# tiny-usb.net
KiCad netlist of a schematic drawn in EAGLE
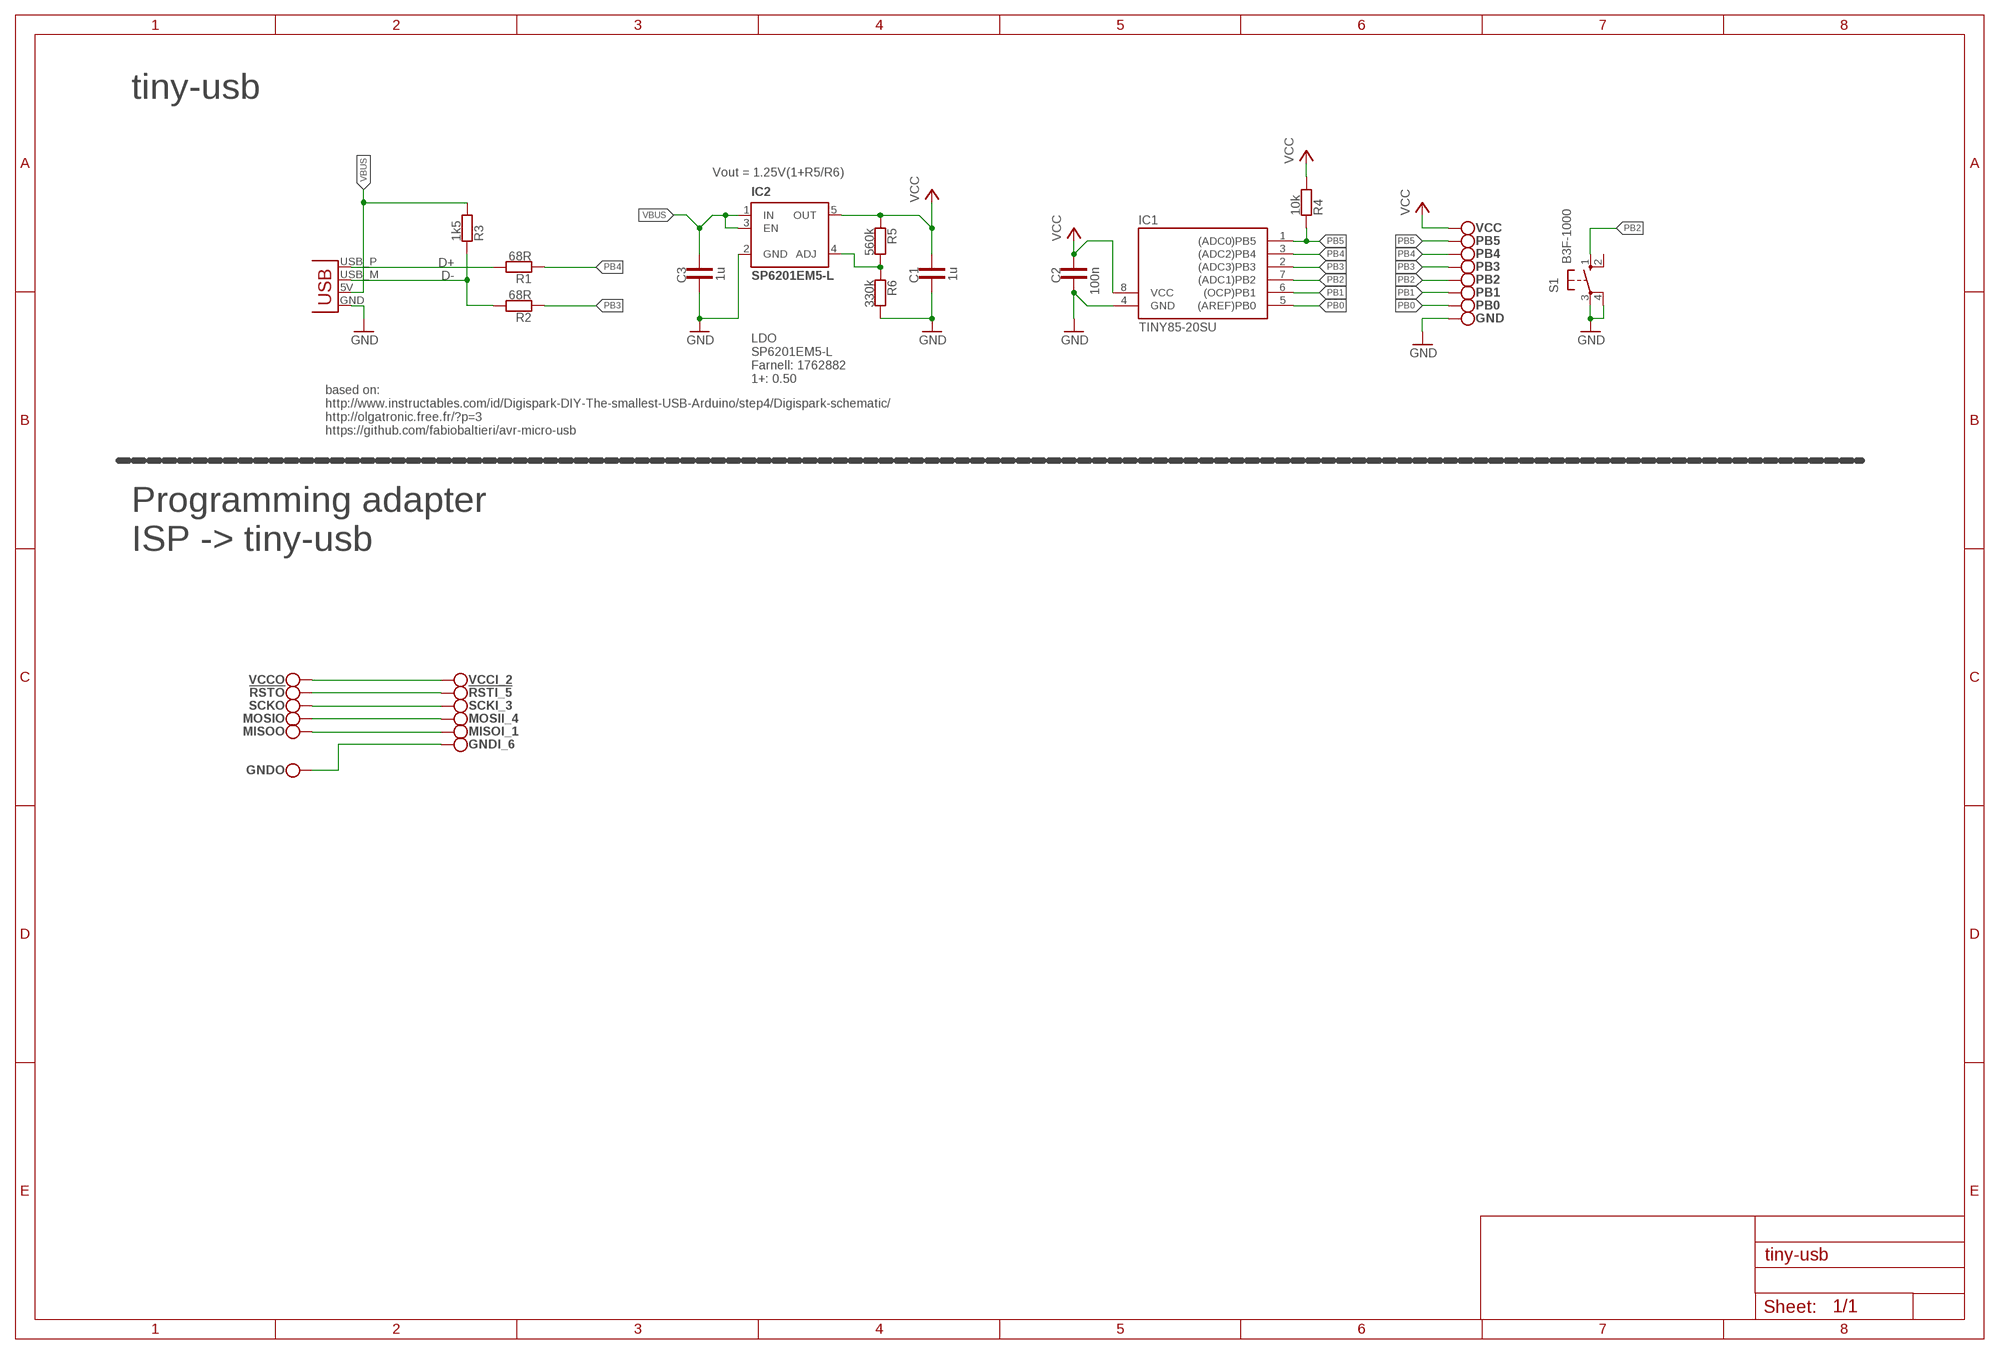
[diagram p0: schematic, sheet 1]

(export (version "E")
  (design (tool "Eeschema 10.0.6"))
  (components
    (comp (ref "!RSTI_5")
      (value "TP_Q3X1.5MM")
      (footprint "eagle-import:PAD_Q1.5X3MM")
      (libsource (lib "eagle-import") (part "TP_Q3X1.5MM"))
    )
    (comp (ref "!RSTO")
      (value "TP_Q3X1.5MM")
      (footprint "eagle-import:PAD_Q1.5X3MM")
      (libsource (lib "eagle-import") (part "TP_Q3X1.5MM"))
    )
    (comp (ref "C1")
      (value "1u")
      (footprint "eagle-import:0603MIL")
      (libsource (lib "eagle-import") (part "C0603"))
    )
    (comp (ref "C2")
      (value "100n")
      (footprint "eagle-import:0603MIL")
      (libsource (lib "eagle-import") (part "C0603"))
    )
    (comp (ref "C3")
      (value "1u")
      (footprint "eagle-import:0603MIL")
      (libsource (lib "eagle-import") (part "C0603"))
    )
    (comp (ref "GND")
      (value "TP_Q3X1.5MM")
      (footprint "eagle-import:PAD_Q1.5X3MM")
      (libsource (lib "eagle-import") (part "TP_Q3X1.5MM"))
    )
    (comp (ref "GNDI_6")
      (value "TP_Q3X1.5MM")
      (footprint "eagle-import:PAD_Q1.5X3MM")
      (libsource (lib "eagle-import") (part "TP_Q3X1.5MM"))
    )
    (comp (ref "GNDO")
      (value "TP_Q3X1.5MM")
      (footprint "eagle-import:PAD_Q1.5X3MM")
      (libsource (lib "eagle-import") (part "TP_Q3X1.5MM"))
    )
    (comp (ref "IC1")
      (value "TINY85-20SU")
      (footprint "eagle-import:SOIC8")
      (libsource (lib "eagle-import") (part "TINY25-20SU"))
    )
    (comp (ref "IC2")
      (value "SP6201EM5-L")
      (footprint "eagle-import:SOT23-5")
      (libsource (lib "eagle-import") (part "SP6201EM5-L"))
    )
    (comp (ref "MISOI_1")
      (value "TP_Q3X1.5MM")
      (footprint "eagle-import:PAD_Q1.5X3MM")
      (libsource (lib "eagle-import") (part "TP_Q3X1.5MM"))
    )
    (comp (ref "MISOO")
      (value "TP_Q3X1.5MM")
      (footprint "eagle-import:PAD_Q1.5X3MM")
      (libsource (lib "eagle-import") (part "TP_Q3X1.5MM"))
    )
    (comp (ref "MOSII_4")
      (value "TP_Q3X1.5MM")
      (footprint "eagle-import:PAD_Q1.5X3MM")
      (libsource (lib "eagle-import") (part "TP_Q3X1.5MM"))
    )
    (comp (ref "MOSIO")
      (value "TP_Q3X1.5MM")
      (footprint "eagle-import:PAD_Q1.5X3MM")
      (libsource (lib "eagle-import") (part "TP_Q3X1.5MM"))
    )
    (comp (ref "PB0")
      (value "TP_Q3X1.5MM")
      (footprint "eagle-import:PAD_Q1.5X3MM")
      (libsource (lib "eagle-import") (part "TP_Q3X1.5MM"))
    )
    (comp (ref "PB1")
      (value "TP_Q3X1.5MM")
      (footprint "eagle-import:PAD_Q1.5X3MM")
      (libsource (lib "eagle-import") (part "TP_Q3X1.5MM"))
    )
    (comp (ref "PB2")
      (value "TP_Q3X1.5MM")
      (footprint "eagle-import:PAD_Q1.5X3MM")
      (libsource (lib "eagle-import") (part "TP_Q3X1.5MM"))
    )
    (comp (ref "PB3")
      (value "TP_Q3X1.5MM")
      (footprint "eagle-import:PAD_Q1.5X3MM")
      (libsource (lib "eagle-import") (part "TP_Q3X1.5MM"))
    )
    (comp (ref "PB4")
      (value "TP_Q3X1.5MM")
      (footprint "eagle-import:PAD_Q1.5X3MM")
      (libsource (lib "eagle-import") (part "TP_Q3X1.5MM"))
    )
    (comp (ref "PB5")
      (value "TP_Q3X1.5MM")
      (footprint "eagle-import:PAD_Q1.5X3MM")
      (libsource (lib "eagle-import") (part "TP_Q3X1.5MM"))
    )
    (comp (ref "R1")
      (value "68R")
      (footprint "eagle-import:0603MIL")
      (libsource (lib "eagle-import") (part "R0603"))
    )
    (comp (ref "R2")
      (value "68R")
      (footprint "eagle-import:0603MIL")
      (libsource (lib "eagle-import") (part "R0603"))
    )
    (comp (ref "R3")
      (value "1k5")
      (footprint "eagle-import:0603MIL")
      (libsource (lib "eagle-import") (part "R0603"))
    )
    (comp (ref "R4")
      (value "10k")
      (footprint "eagle-import:0603MIL")
      (libsource (lib "eagle-import") (part "R0603"))
    )
    (comp (ref "R5")
      (value "560k")
      (footprint "eagle-import:0603MIL")
      (libsource (lib "eagle-import") (part "R0603"))
    )
    (comp (ref "R6")
      (value "330k")
      (footprint "eagle-import:0603MIL")
      (libsource (lib "eagle-import") (part "R0603"))
    )
    (comp (ref "S1")
      (value "B3F-1000")
      (footprint "eagle-import:B3F-10SMD")
      (libsource (lib "eagle-import") (part "10-XXSMD"))
    )
    (comp (ref "SCKI_3")
      (value "TP_Q3X1.5MM")
      (footprint "eagle-import:PAD_Q1.5X3MM")
      (libsource (lib "eagle-import") (part "TP_Q3X1.5MM"))
    )
    (comp (ref "SCKO")
      (value "TP_Q3X1.5MM")
      (footprint "eagle-import:PAD_Q1.5X3MM")
      (libsource (lib "eagle-import") (part "TP_Q3X1.5MM"))
    )
    (comp (ref "VCC")
      (value "TP_Q3X1.5MM")
      (footprint "eagle-import:PAD_Q1.5X3MM")
      (libsource (lib "eagle-import") (part "TP_Q3X1.5MM"))
    )
    (comp (ref "VCCI_2")
      (value "TP_Q3X1.5MM")
      (footprint "eagle-import:PAD_Q1.5X3MM")
      (libsource (lib "eagle-import") (part "TP_Q3X1.5MM"))
    )
    (comp (ref "VCCO")
      (value "TP_Q3X1.5MM")
      (footprint "eagle-import:PAD_Q1.5X3MM")
      (libsource (lib "eagle-import") (part "TP_Q3X1.5MM"))
    )
    (comp (ref "X1")
      (value "USBPCB")
      (footprint "eagle-import:USB-A-PCB")
      (libsource (lib "eagle-import") (part "USBPCB"))
    )
  )
  (nets
    (net (code "1") (name "/D+") (class "Default")
      (node (ref "R1") (pin "2") (pinfunction "2_2") (pintype "passive"))
      (node (ref "X1") (pin "USB_P") (pinfunction "D+_USB_P") (pintype "bidirectional"))
    )
    (net (code "2") (name "/D-") (class "Default")
      (node (ref "R2") (pin "2") (pinfunction "2_2") (pintype "passive"))
      (node (ref "R3") (pin "1") (pinfunction "1_1") (pintype "passive"))
      (node (ref "X1") (pin "USB_M") (pinfunction "D-_USB_M") (pintype "bidirectional"))
    )
    (net (code "3") (name "GND") (class "Default")
      (node (ref "C1") (pin "2") (pinfunction "2_2") (pintype "passive"))
      (node (ref "C2") (pin "2") (pinfunction "2_2") (pintype "passive"))
      (node (ref "C3") (pin "2") (pinfunction "2_2") (pintype "passive"))
      (node (ref "GND") (pin "1") (pinfunction "P$1_1") (pintype "bidirectional"))
      (node (ref "IC1") (pin "4") (pinfunction "GND_4") (pintype "power_in"))
      (node (ref "IC2") (pin "2") (pinfunction "GND_2") (pintype "bidirectional"))
      (node (ref "R6") (pin "2") (pinfunction "2_2") (pintype "passive"))
      (node (ref "S1") (pin "3") (pinfunction "P_3") (pintype "passive"))
      (node (ref "S1") (pin "4") (pinfunction "P1_4") (pintype "passive"))
      (node (ref "X1") (pin "GND") (pinfunction "GND_GND") (pintype "bidirectional"))
    )
    (net (code "4") (name "Net-(!RSTI_5-P$1)") (class "Default")
      (node (ref "!RSTI_5") (pin "1") (pinfunction "P$1_1") (pintype "bidirectional"))
      (node (ref "!RSTO") (pin "1") (pinfunction "P$1_1") (pintype "bidirectional"))
    )
    (net (code "5") (name "Net-(GNDI_6-P$1)") (class "Default")
      (node (ref "GNDI_6") (pin "1") (pinfunction "P$1_1") (pintype "bidirectional"))
      (node (ref "GNDO") (pin "1") (pinfunction "P$1_1") (pintype "bidirectional"))
    )
    (net (code "6") (name "Net-(IC2-ADJ)") (class "Default")
      (node (ref "IC2") (pin "4") (pinfunction "ADJ_4") (pintype "bidirectional"))
      (node (ref "R5") (pin "2") (pinfunction "2_2") (pintype "passive"))
      (node (ref "R6") (pin "1") (pinfunction "1_1") (pintype "passive"))
    )
    (net (code "7") (name "Net-(MISOI_1-P$1)") (class "Default")
      (node (ref "MISOI_1") (pin "1") (pinfunction "P$1_1") (pintype "bidirectional"))
      (node (ref "MISOO") (pin "1") (pinfunction "P$1_1") (pintype "bidirectional"))
    )
    (net (code "8") (name "Net-(MOSII_4-P$1)") (class "Default")
      (node (ref "MOSII_4") (pin "1") (pinfunction "P$1_1") (pintype "bidirectional"))
      (node (ref "MOSIO") (pin "1") (pinfunction "P$1_1") (pintype "bidirectional"))
    )
    (net (code "9") (name "Net-(SCKI_3-P$1)") (class "Default")
      (node (ref "SCKI_3") (pin "1") (pinfunction "P$1_1") (pintype "bidirectional"))
      (node (ref "SCKO") (pin "1") (pinfunction "P$1_1") (pintype "bidirectional"))
    )
    (net (code "10") (name "Net-(VCCI_2-P$1)") (class "Default")
      (node (ref "VCCI_2") (pin "1") (pinfunction "P$1_1") (pintype "bidirectional"))
      (node (ref "VCCO") (pin "1") (pinfunction "P$1_1") (pintype "bidirectional"))
    )
    (net (code "11") (name "PB0") (class "Default")
      (node (ref "IC1") (pin "5") (pinfunction "(AREF)PB0_5") (pintype "bidirectional"))
      (node (ref "PB0") (pin "1") (pinfunction "P$1_1") (pintype "bidirectional"))
    )
    (net (code "12") (name "PB1") (class "Default")
      (node (ref "IC1") (pin "6") (pinfunction "(OCP)PB1_6") (pintype "bidirectional"))
      (node (ref "PB1") (pin "1") (pinfunction "P$1_1") (pintype "bidirectional"))
    )
    (net (code "13") (name "PB2") (class "Default")
      (node (ref "IC1") (pin "7") (pinfunction "(ADC1)PB2_7") (pintype "bidirectional"))
      (node (ref "PB2") (pin "1") (pinfunction "P$1_1") (pintype "bidirectional"))
      (node (ref "S1") (pin "1") (pinfunction "S_1") (pintype "passive"))
    )
    (net (code "14") (name "PB3") (class "Default")
      (node (ref "IC1") (pin "2") (pinfunction "(ADC3)PB3_2") (pintype "bidirectional"))
      (node (ref "PB3") (pin "1") (pinfunction "P$1_1") (pintype "bidirectional"))
      (node (ref "R2") (pin "1") (pinfunction "1_1") (pintype "passive"))
    )
    (net (code "15") (name "PB4") (class "Default")
      (node (ref "IC1") (pin "3") (pinfunction "(ADC2)PB4_3") (pintype "bidirectional"))
      (node (ref "PB4") (pin "1") (pinfunction "P$1_1") (pintype "bidirectional"))
      (node (ref "R1") (pin "1") (pinfunction "1_1") (pintype "passive"))
    )
    (net (code "16") (name "PB5") (class "Default")
      (node (ref "IC1") (pin "1") (pinfunction "(ADC0)PB5_1") (pintype "bidirectional"))
      (node (ref "PB5") (pin "1") (pinfunction "P$1_1") (pintype "bidirectional"))
      (node (ref "R4") (pin "1") (pinfunction "1_1") (pintype "passive"))
    )
    (net (code "17") (name "VBUS") (class "Default")
      (node (ref "C3") (pin "1") (pinfunction "1_1") (pintype "passive"))
      (node (ref "IC2") (pin "1") (pinfunction "IN_1") (pintype "bidirectional"))
      (node (ref "IC2") (pin "3") (pinfunction "EN_3") (pintype "bidirectional"))
      (node (ref "R3") (pin "2") (pinfunction "2_2") (pintype "passive"))
      (node (ref "X1") (pin "5V") (pinfunction "VBUS_5V") (pintype "bidirectional"))
    )
    (net (code "18") (name "VCC") (class "Default")
      (node (ref "C1") (pin "1") (pinfunction "1_1") (pintype "passive"))
      (node (ref "C2") (pin "1") (pinfunction "1_1") (pintype "passive"))
      (node (ref "IC1") (pin "8") (pinfunction "VCC_8") (pintype "power_in"))
      (node (ref "IC2") (pin "5") (pinfunction "OUT_5") (pintype "bidirectional"))
      (node (ref "R4") (pin "2") (pinfunction "2_2") (pintype "passive"))
      (node (ref "R5") (pin "1") (pinfunction "1_1") (pintype "passive"))
      (node (ref "VCC") (pin "1") (pinfunction "P$1_1") (pintype "bidirectional"))
    )
    (net (code "19") (name "unconnected-(S1-S1-Pad2)") (class "Default")
      (node (ref "S1") (pin "2") (pinfunction "S1_2") (pintype "passive"))
    )
  )
)
